# Venus638FLPX-L.net
KiCad netlist of a schematic drawn in EAGLE
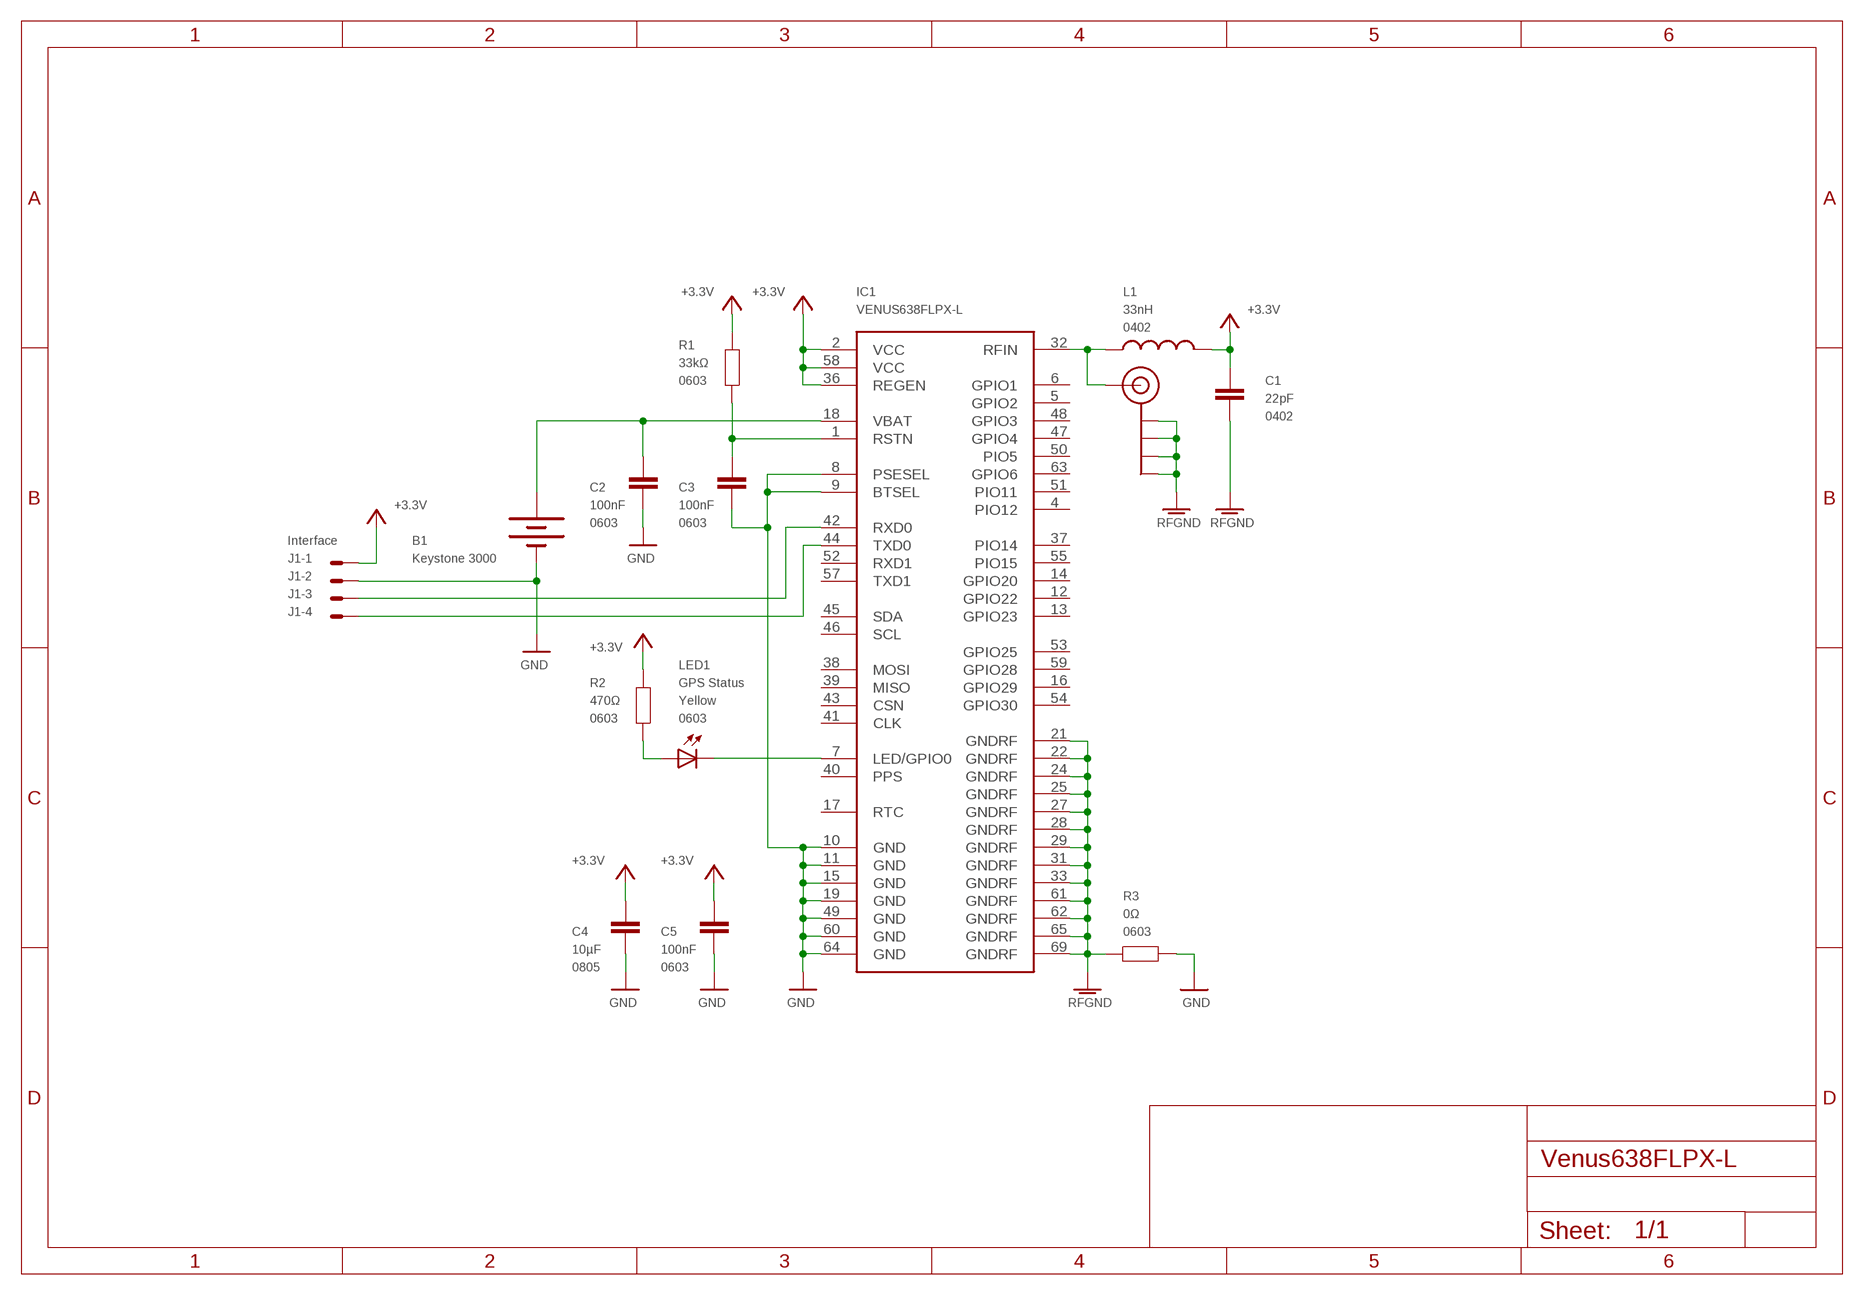
[diagram p0: schematic, sheet 1]

(export (version "E")
  (design (tool "Eeschema 10.0.6"))
  (components
    (comp (ref "B1")
      (value "Keystone 3000")
      (footprint "eagle-import:BATTCON_12MM")
      (libsource (lib "eagle-import") (part "BATTERY12MM"))
    )
    (comp (ref "C1")
      (value "22pF")
      (footprint "eagle-import:C0402")
      (fields (field (name "PACKAGE") "0402"))
      (libsource (lib "eagle-import") (part "CAP0402"))
    )
    (comp (ref "C2")
      (value "100nF")
      (footprint "eagle-import:0603")
      (fields (field (name "PACKAGE") "0603"))
      (libsource (lib "eagle-import") (part "CAP0603"))
    )
    (comp (ref "C3")
      (value "100nF")
      (footprint "eagle-import:0603")
      (fields (field (name "PACKAGE") "0603"))
      (libsource (lib "eagle-import") (part "CAP0603"))
    )
    (comp (ref "C4")
      (value "10µF")
      (footprint "eagle-import:0805")
      (fields (field (name "PACKAGE") "0805"))
      (libsource (lib "eagle-import") (part "CAP0805"))
    )
    (comp (ref "C5")
      (value "100nF")
      (footprint "eagle-import:0603")
      (fields (field (name "PACKAGE") "0603"))
      (libsource (lib "eagle-import") (part "CAP0603"))
    )
    (comp (ref "IC1")
      (value "VENUS638FLPX-L")
      (footprint "eagle-import:VENUS638FLPX")
      (libsource (lib "eagle-import") (part "VENUS638FLPX-L"))
    )
    (comp (ref "J1")
      (value "Interface")
      (footprint "eagle-import:7395-04")
      (libsource (lib "eagle-import") (part "22-?-0405-7048"))
    )
    (comp (ref "JP1")
      (value "Antenna")
      (footprint "eagle-import:SMA-EDGE")
      (libsource (lib "eagle-import") (part "SMA_EDGE"))
    )
    (comp (ref "L1")
      (value "33nH")
      (footprint "eagle-import:C0402")
      (fields (field (name "PACKAGE") "0402"))
      (libsource (lib "eagle-import") (part "INDUCTOR0402"))
    )
    (comp (ref "LED1")
      (value "GPS Status")
      (footprint "eagle-import:LED-0603")
      (fields (field (name "COLOUR") "Yellow") (field (name "PACKAGE") "0603"))
      (libsource (lib "eagle-import") (part "LED0603"))
    )
    (comp (ref "R1")
      (value "33kΩ")
      (footprint "eagle-import:0603")
      (fields (field (name "PACKAGE") "0603"))
      (libsource (lib "eagle-import") (part "RESISTOR0603"))
    )
    (comp (ref "R2")
      (value "470Ω")
      (footprint "eagle-import:0603")
      (fields (field (name "PACKAGE") "0603"))
      (libsource (lib "eagle-import") (part "RESISTOR0603"))
    )
    (comp (ref "R3")
      (value "0Ω")
      (footprint "eagle-import:0603")
      (fields (field (name "PACKAGE") "0603"))
      (libsource (lib "eagle-import") (part "RESISTOR0603"))
    )
  )
  (nets
    (net (code "1") (name "+3.3V") (class "Default")
      (node (ref "C1") (pin "2") (pinfunction "2_2") (pintype "passive"))
      (node (ref "C4") (pin "2") (pinfunction "2_2") (pintype "passive"))
      (node (ref "C5") (pin "2") (pinfunction "2_2") (pintype "passive"))
      (node (ref "IC1") (pin "2") (pinfunction "VCC_2") (pintype "bidirectional"))
      (node (ref "IC1") (pin "36") (pinfunction "REGEN_36") (pintype "bidirectional"))
      (node (ref "IC1") (pin "58") (pinfunction "VCC_58") (pintype "bidirectional"))
      (node (ref "J1") (pin "1") (pinfunction "S_1") (pintype "passive"))
      (node (ref "L1") (pin "1") (pinfunction "1_1") (pintype "passive"))
      (node (ref "R1") (pin "1") (pinfunction "1_1") (pintype "passive"))
      (node (ref "R2") (pin "1") (pinfunction "1_1") (pintype "passive"))
    )
    (net (code "2") (name "GND") (class "Default")
      (node (ref "B1") (pin "GND") (pinfunction "-_GND") (pintype "power_in"))
      (node (ref "C2") (pin "1") (pinfunction "1_1") (pintype "passive"))
      (node (ref "C3") (pin "1") (pinfunction "1_1") (pintype "passive"))
      (node (ref "C4") (pin "1") (pinfunction "1_1") (pintype "passive"))
      (node (ref "C5") (pin "1") (pinfunction "1_1") (pintype "passive"))
      (node (ref "IC1") (pin "10") (pinfunction "GND_10") (pintype "bidirectional"))
      (node (ref "IC1") (pin "11") (pinfunction "GND_11") (pintype "bidirectional"))
      (node (ref "IC1") (pin "15") (pinfunction "GND_15") (pintype "bidirectional"))
      (node (ref "IC1") (pin "19") (pinfunction "GND_19") (pintype "bidirectional"))
      (node (ref "IC1") (pin "49") (pinfunction "GND_49") (pintype "bidirectional"))
      (node (ref "IC1") (pin "60") (pinfunction "GND_60") (pintype "bidirectional"))
      (node (ref "IC1") (pin "64") (pinfunction "GND_64") (pintype "bidirectional"))
      (node (ref "IC1") (pin "8") (pinfunction "PSESEL_8") (pintype "bidirectional"))
      (node (ref "IC1") (pin "9") (pinfunction "BTSEL_9") (pintype "bidirectional"))
      (node (ref "J1") (pin "2") (pinfunction "S_2") (pintype "passive"))
      (node (ref "R3") (pin "1") (pinfunction "1_1") (pintype "passive"))
    )
    (net (code "3") (name "Net-(B1-+)") (class "Default")
      (node (ref "B1") (pin "PWR@1") (pinfunction "+_PWR@1") (pintype "power_in"))
      (node (ref "C2") (pin "2") (pinfunction "2_2") (pintype "passive"))
      (node (ref "IC1") (pin "18") (pinfunction "VBAT_18") (pintype "bidirectional"))
    )
    (net (code "4") (name "Net-(IC1-LED{slash}GPIO0)") (class "Default")
      (node (ref "IC1") (pin "7") (pinfunction "LED/GPIO0_7") (pintype "bidirectional"))
      (node (ref "LED1") (pin "C") (pinfunction "C_C") (pintype "passive"))
    )
    (net (code "5") (name "Net-(IC1-RFIN)") (class "Default")
      (node (ref "IC1") (pin "32") (pinfunction "RFIN_32") (pintype "bidirectional"))
      (node (ref "JP1") (pin "SIG") (pinfunction "SIGNAL_SIG") (pintype "bidirectional"))
      (node (ref "L1") (pin "2") (pinfunction "2_2") (pintype "passive"))
    )
    (net (code "6") (name "Net-(IC1-RSTN)") (class "Default")
      (node (ref "C3") (pin "2") (pinfunction "2_2") (pintype "passive"))
      (node (ref "IC1") (pin "1") (pinfunction "RSTN_1") (pintype "bidirectional"))
      (node (ref "R1") (pin "2") (pinfunction "2_2") (pintype "passive"))
    )
    (net (code "7") (name "Net-(IC1-RXD0)") (class "Default")
      (node (ref "IC1") (pin "42") (pinfunction "RXD0_42") (pintype "bidirectional"))
      (node (ref "J1") (pin "3") (pinfunction "S_3") (pintype "passive"))
    )
    (net (code "8") (name "Net-(IC1-TXD0)") (class "Default")
      (node (ref "IC1") (pin "44") (pinfunction "TXD0_44") (pintype "bidirectional"))
      (node (ref "J1") (pin "4") (pinfunction "S_4") (pintype "passive"))
    )
    (net (code "9") (name "Net-(LED1-PadA)") (class "Default")
      (node (ref "LED1") (pin "A") (pinfunction "A_A") (pintype "passive"))
      (node (ref "R2") (pin "2") (pinfunction "2_2") (pintype "passive"))
    )
    (net (code "10") (name "RFGND") (class "Default")
      (node (ref "C1") (pin "1") (pinfunction "1_1") (pintype "passive"))
      (node (ref "IC1") (pin "21") (pinfunction "GNDRF_21") (pintype "bidirectional"))
      (node (ref "IC1") (pin "22") (pinfunction "GNDRF_22") (pintype "bidirectional"))
      (node (ref "IC1") (pin "24") (pinfunction "GNDRF_24") (pintype "bidirectional"))
      (node (ref "IC1") (pin "25") (pinfunction "GNDRF_25") (pintype "bidirectional"))
      (node (ref "IC1") (pin "27") (pinfunction "GNDRF_27") (pintype "bidirectional"))
      (node (ref "IC1") (pin "28") (pinfunction "GNDRF_28") (pintype "bidirectional"))
      (node (ref "IC1") (pin "29") (pinfunction "GNDRF_29") (pintype "bidirectional"))
      (node (ref "IC1") (pin "31") (pinfunction "GNDRF_31") (pintype "bidirectional"))
      (node (ref "IC1") (pin "33") (pinfunction "GNDRF_33") (pintype "bidirectional"))
      (node (ref "IC1") (pin "61") (pinfunction "GNDRF_61") (pintype "bidirectional"))
      (node (ref "IC1") (pin "62") (pinfunction "GNDRF_62") (pintype "bidirectional"))
      (node (ref "IC1") (pin "65") (pinfunction "GNDRF_65") (pintype "bidirectional"))
      (node (ref "IC1") (pin "69") (pinfunction "GNDRF_69") (pintype "bidirectional"))
      (node (ref "JP1") (pin "GND@0") (pinfunction "GND_GND@0") (pintype "bidirectional"))
      (node (ref "JP1") (pin "GND@1") (pinfunction "GND_GND@1") (pintype "bidirectional"))
      (node (ref "JP1") (pin "GND@2") (pinfunction "GND_GND@2") (pintype "bidirectional"))
      (node (ref "JP1") (pin "GND@3") (pinfunction "GND_GND@3") (pintype "bidirectional"))
      (node (ref "R3") (pin "2") (pinfunction "2_2") (pintype "passive"))
    )
    (net (code "11") (name "unconnected-(IC1-CLK-Pad41)") (class "Default")
      (node (ref "IC1") (pin "41") (pinfunction "CLK_41") (pintype "bidirectional"))
    )
    (net (code "12") (name "unconnected-(IC1-CSN-Pad43)") (class "Default")
      (node (ref "IC1") (pin "43") (pinfunction "CSN_43") (pintype "bidirectional"))
    )
    (net (code "13") (name "unconnected-(IC1-GPIO1-Pad6)") (class "Default")
      (node (ref "IC1") (pin "6") (pinfunction "GPIO1_6") (pintype "bidirectional"))
    )
    (net (code "14") (name "unconnected-(IC1-GPIO2-Pad5)") (class "Default")
      (node (ref "IC1") (pin "5") (pinfunction "GPIO2_5") (pintype "bidirectional"))
    )
    (net (code "15") (name "unconnected-(IC1-GPIO3-Pad48)") (class "Default")
      (node (ref "IC1") (pin "48") (pinfunction "GPIO3_48") (pintype "bidirectional"))
    )
    (net (code "16") (name "unconnected-(IC1-GPIO4-Pad47)") (class "Default")
      (node (ref "IC1") (pin "47") (pinfunction "GPIO4_47") (pintype "bidirectional"))
    )
    (net (code "17") (name "unconnected-(IC1-GPIO6-Pad63)") (class "Default")
      (node (ref "IC1") (pin "63") (pinfunction "GPIO6_63") (pintype "bidirectional"))
    )
    (net (code "18") (name "unconnected-(IC1-GPIO20-Pad14)") (class "Default")
      (node (ref "IC1") (pin "14") (pinfunction "GPIO20_14") (pintype "bidirectional"))
    )
    (net (code "19") (name "unconnected-(IC1-GPIO22-Pad12)") (class "Default")
      (node (ref "IC1") (pin "12") (pinfunction "GPIO22_12") (pintype "bidirectional"))
    )
    (net (code "20") (name "unconnected-(IC1-GPIO23-Pad13)") (class "Default")
      (node (ref "IC1") (pin "13") (pinfunction "GPIO23_13") (pintype "bidirectional"))
    )
    (net (code "21") (name "unconnected-(IC1-GPIO25-Pad53)") (class "Default")
      (node (ref "IC1") (pin "53") (pinfunction "GPIO25_53") (pintype "bidirectional"))
    )
    (net (code "22") (name "unconnected-(IC1-GPIO28-Pad59)") (class "Default")
      (node (ref "IC1") (pin "59") (pinfunction "GPIO28_59") (pintype "bidirectional"))
    )
    (net (code "23") (name "unconnected-(IC1-GPIO29-Pad16)") (class "Default")
      (node (ref "IC1") (pin "16") (pinfunction "GPIO29_16") (pintype "bidirectional"))
    )
    (net (code "24") (name "unconnected-(IC1-GPIO30-Pad54)") (class "Default")
      (node (ref "IC1") (pin "54") (pinfunction "GPIO30_54") (pintype "bidirectional"))
    )
    (net (code "25") (name "unconnected-(IC1-MISO-Pad39)") (class "Default")
      (node (ref "IC1") (pin "39") (pinfunction "MISO_39") (pintype "bidirectional"))
    )
    (net (code "26") (name "unconnected-(IC1-MOSI-Pad38)") (class "Default")
      (node (ref "IC1") (pin "38") (pinfunction "MOSI_38") (pintype "bidirectional"))
    )
    (net (code "27") (name "unconnected-(IC1-PIO5-Pad50)") (class "Default")
      (node (ref "IC1") (pin "50") (pinfunction "PIO5_50") (pintype "bidirectional"))
    )
    (net (code "28") (name "unconnected-(IC1-PIO11-Pad51)") (class "Default")
      (node (ref "IC1") (pin "51") (pinfunction "PIO11_51") (pintype "bidirectional"))
    )
    (net (code "29") (name "unconnected-(IC1-PIO12-Pad4)") (class "Default")
      (node (ref "IC1") (pin "4") (pinfunction "PIO12_4") (pintype "bidirectional"))
    )
    (net (code "30") (name "unconnected-(IC1-PIO14-Pad37)") (class "Default")
      (node (ref "IC1") (pin "37") (pinfunction "PIO14_37") (pintype "bidirectional"))
    )
    (net (code "31") (name "unconnected-(IC1-PIO15-Pad55)") (class "Default")
      (node (ref "IC1") (pin "55") (pinfunction "PIO15_55") (pintype "bidirectional"))
    )
    (net (code "32") (name "unconnected-(IC1-PPS-Pad40)") (class "Default")
      (node (ref "IC1") (pin "40") (pinfunction "PPS_40") (pintype "bidirectional"))
    )
    (net (code "33") (name "unconnected-(IC1-RTC-Pad17)") (class "Default")
      (node (ref "IC1") (pin "17") (pinfunction "RTC_17") (pintype "bidirectional"))
    )
    (net (code "34") (name "unconnected-(IC1-RXD1-Pad52)") (class "Default")
      (node (ref "IC1") (pin "52") (pinfunction "RXD1_52") (pintype "bidirectional"))
    )
    (net (code "35") (name "unconnected-(IC1-SCL-Pad46)") (class "Default")
      (node (ref "IC1") (pin "46") (pinfunction "SCL_46") (pintype "bidirectional"))
    )
    (net (code "36") (name "unconnected-(IC1-SDA-Pad45)") (class "Default")
      (node (ref "IC1") (pin "45") (pinfunction "SDA_45") (pintype "bidirectional"))
    )
    (net (code "37") (name "unconnected-(IC1-TXD1-Pad57)") (class "Default")
      (node (ref "IC1") (pin "57") (pinfunction "TXD1_57") (pintype "bidirectional"))
    )
  )
)
